# IMU.net
KiCad netlist of a schematic drawn in EAGLE
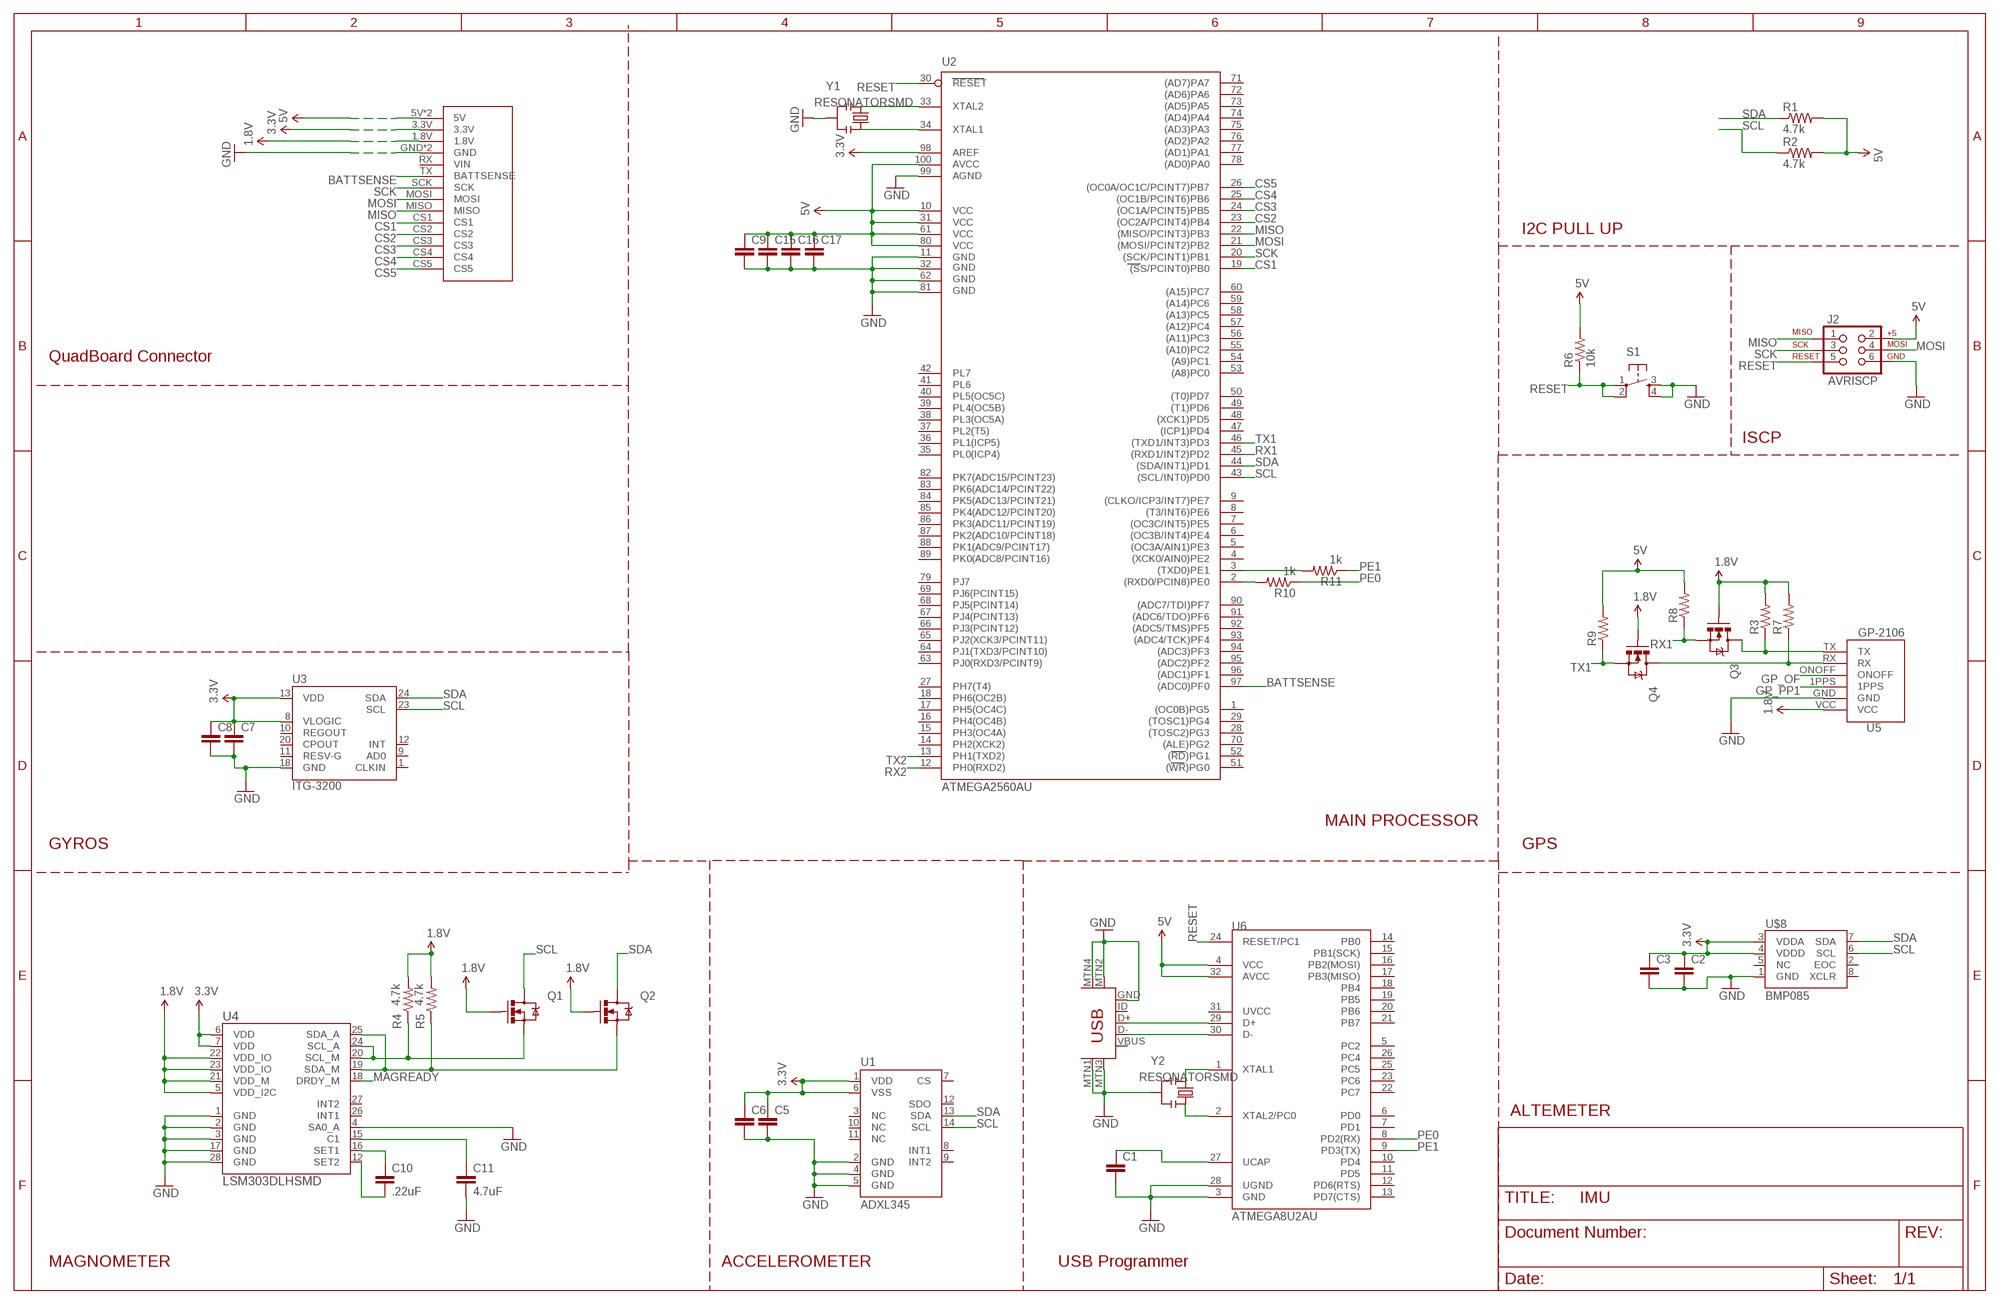
[diagram p0: schematic, sheet 1]

(export (version "E")
  (design (tool "Eeschema 10.0.6"))
  (components
    (comp (ref "C1")
      (value "CAP0805")
      (footprint "eagle-import:0805")
      (libsource (lib "eagle-import") (part "CAP0805"))
    )
    (comp (ref "C2")
      (value "CAP0805")
      (footprint "eagle-import:0805")
      (libsource (lib "eagle-import") (part "CAP0805"))
    )
    (comp (ref "C3")
      (value "CAP0805")
      (footprint "eagle-import:0805")
      (libsource (lib "eagle-import") (part "CAP0805"))
    )
    (comp (ref "C5")
      (value "CAP0805")
      (footprint "eagle-import:0805")
      (libsource (lib "eagle-import") (part "CAP0805"))
    )
    (comp (ref "C6")
      (value "CAP0805")
      (footprint "eagle-import:0805")
      (libsource (lib "eagle-import") (part "CAP0805"))
    )
    (comp (ref "C7")
      (value "CAP0805")
      (footprint "eagle-import:0805")
      (libsource (lib "eagle-import") (part "CAP0805"))
    )
    (comp (ref "C8")
      (value "CAP0805")
      (footprint "eagle-import:0805")
      (libsource (lib "eagle-import") (part "CAP0805"))
    )
    (comp (ref "C9")
      (value "CAP0805")
      (footprint "eagle-import:0805")
      (libsource (lib "eagle-import") (part "CAP0805"))
    )
    (comp (ref "C10")
      (value ".22uF")
      (footprint "eagle-import:0805")
      (libsource (lib "eagle-import") (part "CAP0805"))
    )
    (comp (ref "C11")
      (value "4.7uF")
      (footprint "eagle-import:0805")
      (libsource (lib "eagle-import") (part "CAP0805"))
    )
    (comp (ref "C15")
      (value "CAP0805")
      (footprint "eagle-import:0805")
      (libsource (lib "eagle-import") (part "CAP0805"))
    )
    (comp (ref "C16")
      (value "CAP0805")
      (footprint "eagle-import:0805")
      (libsource (lib "eagle-import") (part "CAP0805"))
    )
    (comp (ref "C17")
      (value "CAP0805")
      (footprint "eagle-import:0805")
      (libsource (lib "eagle-import") (part "CAP0805"))
    )
    (comp (ref "J2")
      (value "AVRISCP")
      (footprint "eagle-import:2X3")
      (libsource (lib "eagle-import") (part "AVR_SPI_PRG_6PTH"))
    )
    (comp (ref "Q1")
      (value "MOSFET-NCHANNELSMD")
      (footprint "eagle-import:SOT23-3")
      (libsource (lib "eagle-import") (part "MOSFET-NCHANNELSMD"))
    )
    (comp (ref "Q2")
      (value "MOSFET-NCHANNELSMD")
      (footprint "eagle-import:SOT23-3")
      (libsource (lib "eagle-import") (part "MOSFET-NCHANNELSMD"))
    )
    (comp (ref "Q3")
      (value "MOSFET-NCHANNELSMD")
      (footprint "eagle-import:SOT23-3")
      (libsource (lib "eagle-import") (part "MOSFET-NCHANNELSMD"))
    )
    (comp (ref "Q4")
      (value "MOSFET-NCHANNELSMD")
      (footprint "eagle-import:SOT23-3")
      (libsource (lib "eagle-import") (part "MOSFET-NCHANNELSMD"))
    )
    (comp (ref "R1")
      (value "4.7k")
      (footprint "eagle-import:0805")
      (libsource (lib "eagle-import") (part "RESISTOR0805-RES"))
    )
    (comp (ref "R2")
      (value "4.7k")
      (footprint "eagle-import:0805")
      (libsource (lib "eagle-import") (part "RESISTOR0805-RES"))
    )
    (comp (ref "R3")
      (value "RESISTOR0805-RES")
      (footprint "eagle-import:0805")
      (libsource (lib "eagle-import") (part "RESISTOR0805-RES"))
    )
    (comp (ref "R4")
      (value "4.7k")
      (footprint "eagle-import:0805")
      (libsource (lib "eagle-import") (part "RESISTOR0805-RES"))
    )
    (comp (ref "R5")
      (value "4.7k")
      (footprint "eagle-import:0805")
      (libsource (lib "eagle-import") (part "RESISTOR0805-RES"))
    )
    (comp (ref "R6")
      (value "10k")
      (footprint "eagle-import:0805")
      (libsource (lib "eagle-import") (part "RESISTOR0805-RES"))
    )
    (comp (ref "R7")
      (value "RESISTOR0805-RES")
      (footprint "eagle-import:0805")
      (libsource (lib "eagle-import") (part "RESISTOR0805-RES"))
    )
    (comp (ref "R8")
      (value "RESISTOR0805-RES")
      (footprint "eagle-import:0805")
      (libsource (lib "eagle-import") (part "RESISTOR0805-RES"))
    )
    (comp (ref "R9")
      (value "RESISTOR0805-RES")
      (footprint "eagle-import:0805")
      (libsource (lib "eagle-import") (part "RESISTOR0805-RES"))
    )
    (comp (ref "R10")
      (value "1k")
      (footprint "eagle-import:0805")
      (libsource (lib "eagle-import") (part "RESISTOR0805-RES"))
    )
    (comp (ref "R11")
      (value "1k")
      (footprint "eagle-import:0805")
      (libsource (lib "eagle-import") (part "RESISTOR0805-RES"))
    )
    (comp (ref "S1")
      (value "TAC_SWITCHSMD")
      (footprint "eagle-import:TACTILE_SWITCH_SMD")
      (libsource (lib "eagle-import") (part "TAC_SWITCHSMD"))
    )
    (comp (ref "U$1")
      (value "USB-MINIB-5PIN")
      (footprint "eagle-import:USB-MINIB")
      (libsource (lib "eagle-import") (part "USB-MINIB-5PIN"))
    )
    (comp (ref "U$4")
      (value "QUADBOARDEXT")
      (footprint "eagle-import:QUADBOARDEXT")
      (libsource (lib "eagle-import") (part "QUADBOARDEXT"))
    )
    (comp (ref "U$8")
      (value "BMP085")
      (footprint "eagle-import:BMP085")
      (libsource (lib "eagle-import") (part "BMP085"))
    )
    (comp (ref "U1")
      (value "ADXL345")
      (footprint "eagle-import:LGA14")
      (libsource (lib "eagle-import") (part "ADXL345"))
    )
    (comp (ref "U2")
      (value "ATMEGA2560AU")
      (footprint "eagle-import:TQFP100")
      (libsource (lib "eagle-import") (part "ATMEGA2560AU"))
    )
    (comp (ref "U3")
      (value "ITG-3200")
      (footprint "eagle-import:QFN-24")
      (libsource (lib "eagle-import") (part "ITG-3200"))
    )
    (comp (ref "U4")
      (value "LSM303DLHSMD")
      (footprint "eagle-import:LGA28-5X5")
      (libsource (lib "eagle-import") (part "LSM303DLHSMD"))
    )
    (comp (ref "U5")
      (value "GP-2106")
      (footprint "eagle-import:GP-2106")
      (libsource (lib "eagle-import") (part "GP-2106"))
    )
    (comp (ref "U6")
      (value "ATMEGA8U2AU")
      (footprint "eagle-import:TQFP32-08")
      (libsource (lib "eagle-import") (part "ATMEGA8U2AU"))
    )
    (comp (ref "Y1")
      (value "RESONATORSMD")
      (footprint "eagle-import:RESONATOR-SMD")
      (libsource (lib "eagle-import") (part "RESONATORSMD"))
    )
    (comp (ref "Y2")
      (value "RESONATORSMD")
      (footprint "eagle-import:RESONATOR-SMD")
      (libsource (lib "eagle-import") (part "RESONATORSMD"))
    )
  )
  (nets
    (net (code "1") (name "/BATTSENSE") (class "Default")
      (node (ref "U$4") (pin "TX") (pinfunction "BATTSENSE_TX") (pintype "bidirectional"))
      (node (ref "U2") (pin "97") (pinfunction "(ADC0)PF0_97") (pintype "bidirectional"))
    )
    (net (code "2") (name "/CS1") (class "Default")
      (node (ref "U$4") (pin "CS1") (pinfunction "CS1_CS1") (pintype "bidirectional"))
      (node (ref "U2") (pin "19") (pinfunction "(SS/PCINT0)PB0_19") (pintype "bidirectional"))
    )
    (net (code "3") (name "/CS2") (class "Default")
      (node (ref "U$4") (pin "CS2") (pinfunction "CS2_CS2") (pintype "bidirectional"))
      (node (ref "U2") (pin "23") (pinfunction "(OC2A/PCINT4)PB4_23") (pintype "bidirectional"))
    )
    (net (code "4") (name "/CS3") (class "Default")
      (node (ref "U$4") (pin "CS3") (pinfunction "CS3_CS3") (pintype "bidirectional"))
      (node (ref "U2") (pin "24") (pinfunction "(OC1A/PCINT5)PB5_24") (pintype "bidirectional"))
    )
    (net (code "5") (name "/CS4") (class "Default")
      (node (ref "U$4") (pin "CS4") (pinfunction "CS4_CS4") (pintype "bidirectional"))
      (node (ref "U2") (pin "25") (pinfunction "(OC1B/PCINT6)PB6_25") (pintype "bidirectional"))
    )
    (net (code "6") (name "/CS5") (class "Default")
      (node (ref "U$4") (pin "CS5") (pinfunction "CS5_CS5") (pintype "bidirectional"))
      (node (ref "U2") (pin "26") (pinfunction "(OC0A/OC1C/PCINT7)PB7_26") (pintype "bidirectional"))
    )
    (net (code "7") (name "/GP_OF") (class "Default")
      (node (ref "U5") (pin "ONOFF") (pinfunction "ONOFF_ONOFF") (pintype "bidirectional"))
    )
    (net (code "8") (name "/GP_PP1") (class "Default")
      (node (ref "U5") (pin "1PPS") (pinfunction "1PPS_1PPS") (pintype "bidirectional"))
    )
    (net (code "9") (name "/MAGREADY") (class "Default")
      (node (ref "U4") (pin "18") (pinfunction "DRDY_M_18") (pintype "bidirectional"))
    )
    (net (code "10") (name "/MISO") (class "Default")
      (node (ref "J2") (pin "1") (pinfunction "1_1") (pintype "passive"))
      (node (ref "U$4") (pin "MISO") (pinfunction "MISO_MISO") (pintype "bidirectional"))
      (node (ref "U2") (pin "22") (pinfunction "(MISO/PCINT3)PB3_22") (pintype "bidirectional"))
    )
    (net (code "11") (name "/MOSI") (class "Default")
      (node (ref "J2") (pin "4") (pinfunction "4_4") (pintype "passive"))
      (node (ref "U$4") (pin "MOSI") (pinfunction "MOSI_MOSI") (pintype "bidirectional"))
      (node (ref "U2") (pin "21") (pinfunction "(MOSI/PCINT2)PB2_21") (pintype "bidirectional"))
    )
    (net (code "12") (name "/PE0") (class "Default")
      (node (ref "R10") (pin "1") (pinfunction "1_1") (pintype "passive"))
      (node (ref "U6") (pin "8") (pinfunction "PD2(RX)_8") (pintype "bidirectional"))
    )
    (net (code "13") (name "/PE1") (class "Default")
      (node (ref "R11") (pin "1") (pinfunction "1_1") (pintype "passive"))
      (node (ref "U6") (pin "9") (pinfunction "PD3(TX)_9") (pintype "bidirectional"))
    )
    (net (code "14") (name "/RESET") (class "Default")
      (node (ref "J2") (pin "5") (pinfunction "5_5") (pintype "passive"))
      (node (ref "R6") (pin "1") (pinfunction "1_1") (pintype "passive"))
      (node (ref "S1") (pin "1") (pinfunction "1_1") (pintype "passive"))
      (node (ref "S1") (pin "2") (pinfunction "2_2") (pintype "passive"))
      (node (ref "U2") (pin "30") (pinfunction "RESET_30") (pintype "input"))
      (node (ref "U6") (pin "24") (pinfunction "RESET/PC1_24") (pintype "bidirectional"))
    )
    (net (code "15") (name "/RX1") (class "Default")
      (node (ref "Q3") (pin "2") (pinfunction "S_2") (pintype "passive"))
      (node (ref "R8") (pin "1") (pinfunction "1_1") (pintype "passive"))
      (node (ref "U2") (pin "45") (pinfunction "(RXD1/INT2)PD2_45") (pintype "bidirectional"))
    )
    (net (code "16") (name "/RX2") (class "Default")
      (node (ref "U2") (pin "12") (pinfunction "PH0(RXD2)_12") (pintype "bidirectional"))
    )
    (net (code "17") (name "/SCK") (class "Default")
      (node (ref "J2") (pin "3") (pinfunction "3_3") (pintype "passive"))
      (node (ref "U$4") (pin "SCK") (pinfunction "SCK_SCK") (pintype "bidirectional"))
      (node (ref "U2") (pin "20") (pinfunction "(SCK/PCINT1)PB1_20") (pintype "bidirectional"))
    )
    (net (code "18") (name "/SCL") (class "Default")
      (node (ref "Q1") (pin "3") (pinfunction "D_3") (pintype "passive"))
      (node (ref "R2") (pin "1") (pinfunction "1_1") (pintype "passive"))
      (node (ref "U$8") (pin "6") (pinfunction "SCL_6") (pintype "input"))
      (node (ref "U1") (pin "14") (pinfunction "SCL_14") (pintype "bidirectional"))
      (node (ref "U2") (pin "43") (pinfunction "(SCL/INT0)PD0_43") (pintype "bidirectional"))
      (node (ref "U3") (pin "23") (pinfunction "SCL_23") (pintype "bidirectional"))
    )
    (net (code "19") (name "/SDA") (class "Default")
      (node (ref "Q2") (pin "3") (pinfunction "D_3") (pintype "passive"))
      (node (ref "R1") (pin "1") (pinfunction "1_1") (pintype "passive"))
      (node (ref "U$8") (pin "7") (pinfunction "SDA_7") (pintype "bidirectional"))
      (node (ref "U1") (pin "13") (pinfunction "SDA_13") (pintype "bidirectional"))
      (node (ref "U2") (pin "44") (pinfunction "(SDA/INT1)PD1_44") (pintype "bidirectional"))
      (node (ref "U3") (pin "24") (pinfunction "SDA_24") (pintype "bidirectional"))
    )
    (net (code "20") (name "/TX1") (class "Default")
      (node (ref "Q4") (pin "2") (pinfunction "S_2") (pintype "passive"))
      (node (ref "R9") (pin "1") (pinfunction "1_1") (pintype "passive"))
      (node (ref "U2") (pin "46") (pinfunction "(TXD1/INT3)PD3_46") (pintype "bidirectional"))
    )
    (net (code "21") (name "/TX2") (class "Default")
      (node (ref "U2") (pin "13") (pinfunction "PH1(TXD2)_13") (pintype "bidirectional"))
    )
    (net (code "22") (name "1.8V") (class "Default")
      (node (ref "Q1") (pin "1") (pinfunction "G_1") (pintype "passive"))
      (node (ref "Q2") (pin "1") (pinfunction "G_1") (pintype "passive"))
      (node (ref "Q3") (pin "1") (pinfunction "G_1") (pintype "passive"))
      (node (ref "Q4") (pin "1") (pinfunction "G_1") (pintype "passive"))
      (node (ref "R3") (pin "2") (pinfunction "2_2") (pintype "passive"))
      (node (ref "R4") (pin "2") (pinfunction "2_2") (pintype "passive"))
      (node (ref "R5") (pin "2") (pinfunction "2_2") (pintype "passive"))
      (node (ref "R7") (pin "2") (pinfunction "2_2") (pintype "passive"))
      (node (ref "U$4") (pin "1.8V") (pinfunction "1.8V_1.8V") (pintype "bidirectional"))
      (node (ref "U4") (pin "21") (pinfunction "VDD_M_21") (pintype "bidirectional"))
      (node (ref "U4") (pin "22") (pinfunction "VDD_IO_22") (pintype "bidirectional"))
      (node (ref "U4") (pin "23") (pinfunction "VDD_IO_23") (pintype "bidirectional"))
      (node (ref "U4") (pin "5") (pinfunction "VDD_I2C_5") (pintype "bidirectional"))
      (node (ref "U5") (pin "VCC") (pinfunction "VCC_VCC") (pintype "bidirectional"))
    )
    (net (code "23") (name "3.3V") (class "Default")
      (node (ref "C2") (pin "1") (pinfunction "1_1") (pintype "passive"))
      (node (ref "C3") (pin "1") (pinfunction "1_1") (pintype "passive"))
      (node (ref "C5") (pin "1") (pinfunction "1_1") (pintype "passive"))
      (node (ref "C6") (pin "1") (pinfunction "1_1") (pintype "passive"))
      (node (ref "C7") (pin "1") (pinfunction "1_1") (pintype "passive"))
      (node (ref "C8") (pin "1") (pinfunction "1_1") (pintype "passive"))
      (node (ref "U$4") (pin "3.3V") (pinfunction "3.3V_3.3V") (pintype "bidirectional"))
      (node (ref "U$8") (pin "3") (pinfunction "VDDA_3") (pintype "power_in"))
      (node (ref "U$8") (pin "4") (pinfunction "VDDD_4") (pintype "power_in"))
      (node (ref "U1") (pin "1") (pinfunction "VDD_1") (pintype "bidirectional"))
      (node (ref "U1") (pin "6") (pinfunction "VSS_6") (pintype "bidirectional"))
      (node (ref "U2") (pin "98") (pinfunction "AREF_98") (pintype "bidirectional"))
      (node (ref "U3") (pin "13") (pinfunction "VDD_13") (pintype "bidirectional"))
      (node (ref "U3") (pin "8") (pinfunction "VLOGIC_8") (pintype "bidirectional"))
      (node (ref "U4") (pin "6") (pinfunction "VDD_6") (pintype "bidirectional"))
      (node (ref "U4") (pin "7") (pinfunction "VDD_7") (pintype "bidirectional"))
    )
    (net (code "24") (name "5V") (class "Default")
      (node (ref "C15") (pin "1") (pinfunction "1_1") (pintype "passive"))
      (node (ref "C16") (pin "1") (pinfunction "1_1") (pintype "passive"))
      (node (ref "C17") (pin "1") (pinfunction "1_1") (pintype "passive"))
      (node (ref "C9") (pin "1") (pinfunction "1_1") (pintype "passive"))
      (node (ref "J2") (pin "2") (pinfunction "2_2") (pintype "passive"))
      (node (ref "R1") (pin "2") (pinfunction "2_2") (pintype "passive"))
      (node (ref "R2") (pin "2") (pinfunction "2_2") (pintype "passive"))
      (node (ref "R6") (pin "2") (pinfunction "2_2") (pintype "passive"))
      (node (ref "R8") (pin "2") (pinfunction "2_2") (pintype "passive"))
      (node (ref "R9") (pin "2") (pinfunction "2_2") (pintype "passive"))
      (node (ref "U$4") (pin "5V") (pinfunction "5V_5V") (pintype "bidirectional"))
      (node (ref "U$4") (pin "5V1") (pinfunction "5V_5V1") (pintype "bidirectional"))
      (node (ref "U2") (pin "10") (pinfunction "VCC_10") (pintype "power_in"))
      (node (ref "U2") (pin "100") (pinfunction "AVCC_100") (pintype "power_in"))
      (node (ref "U2") (pin "31") (pinfunction "VCC1_31") (pintype "power_in"))
      (node (ref "U2") (pin "61") (pinfunction "VCC2_61") (pintype "power_in"))
      (node (ref "U2") (pin "80") (pinfunction "VCC3_80") (pintype "power_in"))
      (node (ref "U6") (pin "32") (pinfunction "AVCC_32") (pintype "bidirectional"))
      (node (ref "U6") (pin "4") (pinfunction "VCC_4") (pintype "bidirectional"))
    )
    (net (code "25") (name "GND") (class "Default")
      (node (ref "C1") (pin "2") (pinfunction "2_2") (pintype "passive"))
      (node (ref "C11") (pin "2") (pinfunction "2_2") (pintype "passive"))
      (node (ref "C15") (pin "2") (pinfunction "2_2") (pintype "passive"))
      (node (ref "C16") (pin "2") (pinfunction "2_2") (pintype "passive"))
      (node (ref "C17") (pin "2") (pinfunction "2_2") (pintype "passive"))
      (node (ref "C2") (pin "2") (pinfunction "2_2") (pintype "passive"))
      (node (ref "C3") (pin "2") (pinfunction "2_2") (pintype "passive"))
      (node (ref "C5") (pin "2") (pinfunction "2_2") (pintype "passive"))
      (node (ref "C6") (pin "2") (pinfunction "2_2") (pintype "passive"))
      (node (ref "C7") (pin "2") (pinfunction "2_2") (pintype "passive"))
      (node (ref "C8") (pin "2") (pinfunction "2_2") (pintype "passive"))
      (node (ref "C9") (pin "2") (pinfunction "2_2") (pintype "passive"))
      (node (ref "J2") (pin "6") (pinfunction "6_6") (pintype "passive"))
      (node (ref "S1") (pin "3") (pinfunction "3_3") (pintype "passive"))
      (node (ref "S1") (pin "4") (pinfunction "4_4") (pintype "passive"))
      (node (ref "U$1") (pin "GND") (pinfunction "GND_GND") (pintype "bidirectional"))
      (node (ref "U$1") (pin "MTN1") (pinfunction "MTN2_MTN1") (pintype "bidirectional"))
      (node (ref "U$1") (pin "MTN2") (pinfunction "MTN3_MTN2") (pintype "bidirectional"))
      (node (ref "U$1") (pin "MTN3") (pinfunction "MTN1_MTN3") (pintype "bidirectional"))
      (node (ref "U$1") (pin "MTN4") (pinfunction "MTN4_MTN4") (pintype "bidirectional"))
      (node (ref "U$4") (pin "GND") (pinfunction "GND_GND") (pintype "bidirectional"))
      (node (ref "U$4") (pin "GND1") (pinfunction "GND_GND1") (pintype "bidirectional"))
      (node (ref "U$8") (pin "1") (pinfunction "GND_1") (pintype "power_in"))
      (node (ref "U1") (pin "2") (pinfunction "GND_2") (pintype "bidirectional"))
      (node (ref "U1") (pin "4") (pinfunction "GND_4") (pintype "bidirectional"))
      (node (ref "U1") (pin "5") (pinfunction "GND_5") (pintype "bidirectional"))
      (node (ref "U2") (pin "11") (pinfunction "GND_11") (pintype "power_in"))
      (node (ref "U2") (pin "32") (pinfunction "GND1_32") (pintype "power_in"))
      (node (ref "U2") (pin "62") (pinfunction "GND2_62") (pintype "power_in"))
      (node (ref "U2") (pin "81") (pinfunction "GND3_81") (pintype "power_in"))
      (node (ref "U2") (pin "99") (pinfunction "AGND_99") (pintype "power_in"))
      (node (ref "U3") (pin "18") (pinfunction "GND_18") (pintype "bidirectional"))
      (node (ref "U4") (pin "1") (pinfunction "GND_1") (pintype "bidirectional"))
      (node (ref "U4") (pin "17") (pinfunction "GND_17") (pintype "bidirectional"))
      (node (ref "U4") (pin "2") (pinfunction "GND_2") (pintype "bidirectional"))
      (node (ref "U4") (pin "28") (pinfunction "GND_28") (pintype "bidirectional"))
      (node (ref "U4") (pin "3") (pinfunction "GND_3") (pintype "bidirectional"))
      (node (ref "U4") (pin "4") (pinfunction "SA0_A_4") (pintype "bidirectional"))
      (node (ref "U5") (pin "GND") (pinfunction "GND_GND") (pintype "bidirectional"))
      (node (ref "U6") (pin "28") (pinfunction "UGND_28") (pintype "bidirectional"))
      (node (ref "U6") (pin "3") (pinfunction "GND_3") (pintype "bidirectional"))
      (node (ref "Y1") (pin "2") (pinfunction "2_2") (pintype "passive"))
      (node (ref "Y2") (pin "2") (pinfunction "2_2") (pintype "passive"))
    )
    (net (code "26") (name "Net-(Q1-S)") (class "Default")
      (node (ref "Q1") (pin "2") (pinfunction "S_2") (pintype "passive"))
      (node (ref "R4") (pin "1") (pinfunction "1_1") (pintype "passive"))
      (node (ref "U4") (pin "20") (pinfunction "SCL_M_20") (pintype "bidirectional"))
      (node (ref "U4") (pin "24") (pinfunction "SCL_A_24") (pintype "bidirectional"))
    )
    (net (code "27") (name "Net-(Q2-S)") (class "Default")
      (node (ref "Q2") (pin "2") (pinfunction "S_2") (pintype "passive"))
      (node (ref "R5") (pin "1") (pinfunction "1_1") (pintype "passive"))
      (node (ref "U4") (pin "19") (pinfunction "SDA_M_19") (pintype "bidirectional"))
      (node (ref "U4") (pin "25") (pinfunction "SDA_A_25") (pintype "bidirectional"))
    )
    (net (code "28") (name "Net-(Q3-D)") (class "Default")
      (node (ref "Q3") (pin "3") (pinfunction "D_3") (pintype "passive"))
      (node (ref "R3") (pin "1") (pinfunction "1_1") (pintype "passive"))
      (node (ref "U5") (pin "TX") (pinfunction "TX_TX") (pintype "bidirectional"))
    )
    (net (code "29") (name "Net-(Q4-D)") (class "Default")
      (node (ref "Q4") (pin "3") (pinfunction "D_3") (pintype "passive"))
      (node (ref "R7") (pin "1") (pinfunction "1_1") (pintype "passive"))
      (node (ref "U5") (pin "RX") (pinfunction "RX_RX") (pintype "bidirectional"))
    )
    (net (code "30") (name "Net-(U2-(RXD0{slash}PCIN8)PE0)") (class "Default")
      (node (ref "R10") (pin "2") (pinfunction "2_2") (pintype "passive"))
      (node (ref "U2") (pin "2") (pinfunction "(RXD0/PCIN8)PE0_2") (pintype "bidirectional"))
    )
    (net (code "31") (name "Net-(U2-(TXD0)PE1)") (class "Default")
      (node (ref "R11") (pin "2") (pinfunction "2_2") (pintype "passive"))
      (node (ref "U2") (pin "3") (pinfunction "(TXD0)PE1_3") (pintype "bidirectional"))
    )
    (net (code "32") (name "Net-(U2-XTAL1)") (class "Default")
      (node (ref "U2") (pin "34") (pinfunction "XTAL1_34") (pintype "input"))
      (node (ref "Y1") (pin "3") (pinfunction "3_3") (pintype "passive"))
    )
    (net (code "33") (name "Net-(U2-XTAL2)") (class "Default")
      (node (ref "U2") (pin "33") (pinfunction "XTAL2_33") (pintype "output"))
      (node (ref "Y1") (pin "1") (pinfunction "1_1") (pintype "passive"))
    )
    (net (code "34") (name "Net-(U4-C1)") (class "Default")
      (node (ref "C11") (pin "1") (pinfunction "1_1") (pintype "passive"))
      (node (ref "U4") (pin "15") (pinfunction "C1_15") (pintype "bidirectional"))
    )
    (net (code "35") (name "Net-(U4-SET1)") (class "Default")
      (node (ref "C10") (pin "1") (pinfunction "1_1") (pintype "passive"))
      (node (ref "U4") (pin "16") (pinfunction "SET1_16") (pintype "bidirectional"))
    )
    (net (code "36") (name "Net-(U4-SET2)") (class "Default")
      (node (ref "C10") (pin "2") (pinfunction "2_2") (pintype "passive"))
      (node (ref "U4") (pin "12") (pinfunction "SET2_12") (pintype "bidirectional"))
    )
    (net (code "37") (name "Net-(U6-D+)") (class "Default")
      (node (ref "U$1") (pin "D+") (pinfunction "D+_D+") (pintype "bidirectional"))
      (node (ref "U6") (pin "29") (pinfunction "D+_29") (pintype "bidirectional"))
    )
    (net (code "38") (name "Net-(U6-D-)") (class "Default")
      (node (ref "U$1") (pin "D-") (pinfunction "D-_D-") (pintype "bidirectional"))
      (node (ref "U6") (pin "30") (pinfunction "D-_30") (pintype "bidirectional"))
    )
    (net (code "39") (name "Net-(U6-UCAP)") (class "Default")
      (node (ref "C1") (pin "1") (pinfunction "1_1") (pintype "passive"))
      (node (ref "U6") (pin "27") (pinfunction "UCAP_27") (pintype "bidirectional"))
    )
    (net (code "40") (name "Net-(U6-XTAL1)") (class "Default")
      (node (ref "U6") (pin "1") (pinfunction "XTAL1_1") (pintype "bidirectional"))
      (node (ref "Y2") (pin "1") (pinfunction "1_1") (pintype "passive"))
    )
    (net (code "41") (name "Net-(U6-XTAL2{slash}PC0)") (class "Default")
      (node (ref "U6") (pin "2") (pinfunction "XTAL2/PC0_2") (pintype "bidirectional"))
      (node (ref "Y2") (pin "3") (pinfunction "3_3") (pintype "passive"))
    )
    (net (code "42") (name "unconnected-(U$1-PadID)") (class "Default")
      (node (ref "U$1") (pin "ID") (pinfunction "ID_ID") (pintype "bidirectional"))
    )
    (net (code "43") (name "unconnected-(U$1-PadVBUS)") (class "Default")
      (node (ref "U$1") (pin "VBUS") (pinfunction "VBUS_VBUS") (pintype "bidirectional"))
    )
    (net (code "44") (name "unconnected-(U$4-VIN-PadRX)") (class "Default")
      (node (ref "U$4") (pin "RX") (pinfunction "VIN_RX") (pintype "bidirectional"))
    )
    (net (code "45") (name "unconnected-(U$8-EOC-Pad2)") (class "Default")
      (node (ref "U$8") (pin "2") (pinfunction "EOC_2") (pintype "output"))
    )
    (net (code "46") (name "unconnected-(U$8-NC-Pad5)") (class "Default")
      (node (ref "U$8") (pin "5") (pinfunction "NC_5") (pintype "bidirectional"))
    )
    (net (code "47") (name "unconnected-(U$8-XCLR-Pad8)") (class "Default")
      (node (ref "U$8") (pin "8") (pinfunction "XCLR_8") (pintype "input"))
    )
    (net (code "48") (name "unconnected-(U1-CS-Pad7)") (class "Default")
      (node (ref "U1") (pin "7") (pinfunction "CS_7") (pintype "bidirectional"))
    )
    (net (code "49") (name "unconnected-(U1-INT1-Pad8)") (class "Default")
      (node (ref "U1") (pin "8") (pinfunction "INT1_8") (pintype "bidirectional"))
    )
    (net (code "50") (name "unconnected-(U1-INT2-Pad9)") (class "Default")
      (node (ref "U1") (pin "9") (pinfunction "INT2_9") (pintype "bidirectional"))
    )
    (net (code "51") (name "unconnected-(U1-NC-Pad3)") (class "Default")
      (node (ref "U1") (pin "3") (pinfunction "NC_3") (pintype "bidirectional"))
    )
    (net (code "52") (name "unconnected-(U1-NC-Pad10)") (class "Default")
      (node (ref "U1") (pin "10") (pinfunction "NC_10") (pintype "bidirectional"))
    )
    (net (code "53") (name "unconnected-(U1-NC-Pad11)") (class "Default")
      (node (ref "U1") (pin "11") (pinfunction "NC_11") (pintype "bidirectional"))
    )
    (net (code "54") (name "unconnected-(U1-SDO-Pad12)") (class "Default")
      (node (ref "U1") (pin "12") (pinfunction "SDO_12") (pintype "bidirectional"))
    )
    (net (code "55") (name "unconnected-(U2-(A8)PC0-Pad53)") (class "Default")
      (node (ref "U2") (pin "53") (pinfunction "(A8)PC0_53") (pintype "bidirectional"))
    )
    (net (code "56") (name "unconnected-(U2-(A9)PC1-Pad54)") (class "Default")
      (node (ref "U2") (pin "54") (pinfunction "(A9)PC1_54") (pintype "bidirectional"))
    )
    (net (code "57") (name "unconnected-(U2-(A10)PC2-Pad55)") (class "Default")
      (node (ref "U2") (pin "55") (pinfunction "(A10)PC2_55") (pintype "bidirectional"))
    )
    (net (code "58") (name "unconnected-(U2-(A11)PC3-Pad56)") (class "Default")
      (node (ref "U2") (pin "56") (pinfunction "(A11)PC3_56") (pintype "bidirectional"))
    )
    (net (code "59") (name "unconnected-(U2-(A12)PC4-Pad57)") (class "Default")
      (node (ref "U2") (pin "57") (pinfunction "(A12)PC4_57") (pintype "bidirectional"))
    )
    (net (code "60") (name "unconnected-(U2-(A13)PC5-Pad58)") (class "Default")
      (node (ref "U2") (pin "58") (pinfunction "(A13)PC5_58") (pintype "bidirectional"))
    )
    (net (code "61") (name "unconnected-(U2-(A14)PC6-Pad59)") (class "Default")
      (node (ref "U2") (pin "59") (pinfunction "(A14)PC6_59") (pintype "bidirectional"))
    )
    (net (code "62") (name "unconnected-(U2-(A15)PC7-Pad60)") (class "Default")
      (node (ref "U2") (pin "60") (pinfunction "(A15)PC7_60") (pintype "bidirectional"))
    )
    (net (code "63") (name "unconnected-(U2-(AD0)PA0-Pad78)") (class "Default")
      (node (ref "U2") (pin "78") (pinfunction "(AD0)PA0_78") (pintype "bidirectional"))
    )
    (net (code "64") (name "unconnected-(U2-(AD1)PA1-Pad77)") (class "Default")
      (node (ref "U2") (pin "77") (pinfunction "(AD1)PA1_77") (pintype "bidirectional"))
    )
    (net (code "65") (name "unconnected-(U2-(AD2)PA2-Pad76)") (class "Default")
      (node (ref "U2") (pin "76") (pinfunction "(AD2)PA2_76") (pintype "bidirectional"))
    )
    (net (code "66") (name "unconnected-(U2-(AD3)PA3-Pad75)") (class "Default")
      (node (ref "U2") (pin "75") (pinfunction "(AD3)PA3_75") (pintype "bidirectional"))
    )
    (net (code "67") (name "unconnected-(U2-(AD4)PA4-Pad74)") (class "Default")
      (node (ref "U2") (pin "74") (pinfunction "(AD4)PA4_74") (pintype "bidirectional"))
    )
    (net (code "68") (name "unconnected-(U2-(AD5)PA5-Pad73)") (class "Default")
      (node (ref "U2") (pin "73") (pinfunction "(AD5)PA5_73") (pintype "bidirectional"))
    )
    (net (code "69") (name "unconnected-(U2-(AD6)PA6-Pad72)") (class "Default")
      (node (ref "U2") (pin "72") (pinfunction "(AD6)PA6_72") (pintype "bidirectional"))
    )
    (net (code "70") (name "unconnected-(U2-(AD7)PA7-Pad71)") (class "Default")
      (node (ref "U2") (pin "71") (pinfunction "(AD7)PA7_71") (pintype "bidirectional"))
    )
    (net (code "71") (name "unconnected-(U2-(ADC1)PF1-Pad96)") (class "Default")
      (node (ref "U2") (pin "96") (pinfunction "(ADC1)PF1_96") (pintype "bidirectional"))
    )
    (net (code "72") (name "unconnected-(U2-(ADC2)PF2-Pad95)") (class "Default")
      (node (ref "U2") (pin "95") (pinfunction "(ADC2)PF2_95") (pintype "bidirectional"))
    )
    (net (code "73") (name "unconnected-(U2-(ADC3)PF3-Pad94)") (class "Default")
      (node (ref "U2") (pin "94") (pinfunction "(ADC3)PF3_94") (pintype "bidirectional"))
    )
    (net (code "74") (name "unconnected-(U2-(ADC4{slash}TCK)PF4-Pad93)") (class "Default")
      (node (ref "U2") (pin "93") (pinfunction "(ADC4/TCK)PF4_93") (pintype "bidirectional"))
    )
    (net (code "75") (name "unconnected-(U2-(ADC5{slash}TMS)PF5-Pad92)") (class "Default")
      (node (ref "U2") (pin "92") (pinfunction "(ADC5/TMS)PF5_92") (pintype "bidirectional"))
    )
    (net (code "76") (name "unconnected-(U2-(ADC6{slash}TDO)PF6-Pad91)") (class "Default")
      (node (ref "U2") (pin "91") (pinfunction "(ADC6/TDO)PF6_91") (pintype "bidirectional"))
    )
    (net (code "77") (name "unconnected-(U2-(ADC7{slash}TDI)PF7-Pad90)") (class "Default")
      (node (ref "U2") (pin "90") (pinfunction "(ADC7/TDI)PF7_90") (pintype "bidirectional"))
    )
    (net (code "78") (name "unconnected-(U2-(ALE)PG2-Pad70)") (class "Default")
      (node (ref "U2") (pin "70") (pinfunction "(ALE)PG2_70") (pintype "bidirectional"))
    )
    (net (code "79") (name "unconnected-(U2-(CLKO{slash}ICP3{slash}INT7)PE7-Pad9)") (class "Default")
      (node (ref "U2") (pin "9") (pinfunction "(CLKO/ICP3/INT7)PE7_9") (pintype "bidirectional"))
    )
    (net (code "80") (name "unconnected-(U2-(ICP1)PD4-Pad47)") (class "Default")
      (node (ref "U2") (pin "47") (pinfunction "(ICP1)PD4_47") (pintype "bidirectional"))
    )
    (net (code "81") (name "unconnected-(U2-(OC0B)PG5-Pad1)") (class "Default")
      (node (ref "U2") (pin "1") (pinfunction "(OC0B)PG5_1") (pintype "bidirectional"))
    )
    (net (code "82") (name "unconnected-(U2-(OC3A{slash}AIN1)PE3-Pad5)") (class "Default")
      (node (ref "U2") (pin "5") (pinfunction "(OC3A/AIN1)PE3_5") (pintype "bidirectional"))
    )
    (net (code "83") (name "unconnected-(U2-(OC3B{slash}INT4)PE4-Pad6)") (class "Default")
      (node (ref "U2") (pin "6") (pinfunction "(OC3B/INT4)PE4_6") (pintype "bidirectional"))
    )
    (net (code "84") (name "unconnected-(U2-(OC3C{slash}INT5)PE5-Pad7)") (class "Default")
      (node (ref "U2") (pin "7") (pinfunction "(OC3C/INT5)PE5_7") (pintype "bidirectional"))
    )
    (net (code "85") (name "unconnected-(U2-(RD)PG1-Pad52)") (class "Default")
      (node (ref "U2") (pin "52") (pinfunction "(RD)PG1_52") (pintype "bidirectional"))
    )
    (net (code "86") (name "unconnected-(U2-(T0)PD7-Pad50)") (class "Default")
      (node (ref "U2") (pin "50") (pinfunction "(T0)PD7_50") (pintype "bidirectional"))
    )
    (net (code "87") (name "unconnected-(U2-(T1)PD6-Pad49)") (class "Default")
      (node (ref "U2") (pin "49") (pinfunction "(T1)PD6_49") (pintype "bidirectional"))
    )
    (net (code "88") (name "unconnected-(U2-(T3{slash}INT6)PE6-Pad8)") (class "Default")
      (node (ref "U2") (pin "8") (pinfunction "(T3/INT6)PE6_8") (pintype "bidirectional"))
    )
    (net (code "89") (name "unconnected-(U2-(TOSC1)PG4-Pad29)") (class "Default")
      (node (ref "U2") (pin "29") (pinfunction "(TOSC1)PG4_29") (pintype "bidirectional"))
    )
    (net (code "90") (name "unconnected-(U2-(TOSC2)PG3-Pad28)") (class "Default")
      (node (ref "U2") (pin "28") (pinfunction "(TOSC2)PG3_28") (pintype "bidirectional"))
    )
    (net (code "91") (name "unconnected-(U2-(WR)PG0-Pad51)") (class "Default")
      (node (ref "U2") (pin "51") (pinfunction "(WR)PG0_51") (pintype "bidirectional"))
    )
    (net (code "92") (name "unconnected-(U2-(XCK0{slash}AIN0)PE2-Pad4)") (class "Default")
      (node (ref "U2") (pin "4") (pinfunction "(XCK0/AIN0)PE2_4") (pintype "bidirectional"))
    )
    (net (code "93") (name "unconnected-(U2-(XCK1)PD5-Pad48)") (class "Default")
      (node (ref "U2") (pin "48") (pinfunction "(XCK1)PD5_48") (pintype "bidirectional"))
    )
    (net (code "94") (name "unconnected-(U2-PH2(XCK2)-Pad14)") (class "Default")
      (node (ref "U2") (pin "14") (pinfunction "PH2(XCK2)_14") (pintype "bidirectional"))
    )
    (net (code "95") (name "unconnected-(U2-PH3(OC4A)-Pad15)") (class "Default")
      (node (ref "U2") (pin "15") (pinfunction "PH3(OC4A)_15") (pintype "bidirectional"))
    )
    (net (code "96") (name "unconnected-(U2-PH4(OC4B)-Pad16)") (class "Default")
      (node (ref "U2") (pin "16") (pinfunction "PH4(OC4B)_16") (pintype "bidirectional"))
    )
    (net (code "97") (name "unconnected-(U2-PH5(OC4C)-Pad17)") (class "Default")
      (node (ref "U2") (pin "17") (pinfunction "PH5(OC4C)_17") (pintype "bidirectional"))
    )
    (net (code "98") (name "unconnected-(U2-PH6(OC2B)-Pad18)") (class "Default")
      (node (ref "U2") (pin "18") (pinfunction "PH6(OC2B)_18") (pintype "bidirectional"))
    )
    (net (code "99") (name "unconnected-(U2-PH7(T4)-Pad27)") (class "Default")
      (node (ref "U2") (pin "27") (pinfunction "PH7(T4)_27") (pintype "bidirectional"))
    )
    (net (code "100") (name "unconnected-(U2-PJ0(RXD3{slash}PCINT9)-Pad63)") (class "Default")
      (node (ref "U2") (pin "63") (pinfunction "PJ0(RXD3/PCINT9)_63") (pintype "bidirectional"))
    )
    (net (code "101") (name "unconnected-(U2-PJ1(TXD3{slash}PCINT10)-Pad64)") (class "Default")
      (node (ref "U2") (pin "64") (pinfunction "PJ1(TXD3/PCINT10)_64") (pintype "bidirectional"))
    )
    (net (code "102") (name "unconnected-(U2-PJ2(XCK3{slash}PCINT11)-Pad65)") (class "Default")
      (node (ref "U2") (pin "65") (pinfunction "PJ2(XCK3/PCINT11)_65") (pintype "bidirectional"))
    )
    (net (code "103") (name "unconnected-(U2-PJ3(PCINT12)-Pad66)") (class "Default")
      (node (ref "U2") (pin "66") (pinfunction "PJ3(PCINT12)_66") (pintype "bidirectional"))
    )
    (net (code "104") (name "unconnected-(U2-PJ4(PCINT13)-Pad67)") (class "Default")
      (node (ref "U2") (pin "67") (pinfunction "PJ4(PCINT13)_67") (pintype "bidirectional"))
    )
    (net (code "105") (name "unconnected-(U2-PJ5(PCINT14)-Pad68)") (class "Default")
      (node (ref "U2") (pin "68") (pinfunction "PJ5(PCINT14)_68") (pintype "bidirectional"))
    )
    (net (code "106") (name "unconnected-(U2-PJ6(PCINT15)-Pad69)") (class "Default")
      (node (ref "U2") (pin "69") (pinfunction "PJ6(PCINT15)_69") (pintype "bidirectional"))
    )
    (net (code "107") (name "unconnected-(U2-PJ7-Pad79)") (class "Default")
      (node (ref "U2") (pin "79") (pinfunction "PJ7_79") (pintype "bidirectional"))
    )
    (net (code "108") (name "unconnected-(U2-PK0(ADC8{slash}PCINT16)-Pad89)") (class "Default")
      (node (ref "U2") (pin "89") (pinfunction "PK0(ADC8/PCINT16)_89") (pintype "bidirectional"))
    )
    (net (code "109") (name "unconnected-(U2-PK1(ADC9{slash}PCINT17)-Pad88)") (class "Default")
      (node (ref "U2") (pin "88") (pinfunction "PK1(ADC9/PCINT17)_88") (pintype "bidirectional"))
    )
    (net (code "110") (name "unconnected-(U2-PK2(ADC10{slash}PCINT18)-Pad87)") (class "Default")
      (node (ref "U2") (pin "87") (pinfunction "PK2(ADC10/PCINT18)_87") (pintype "bidirectional"))
    )
    (net (code "111") (name "unconnected-(U2-PK3(ADC11{slash}PCINT19)-Pad86)") (class "Default")
      (node (ref "U2") (pin "86") (pinfunction "PK3(ADC11/PCINT19)_86") (pintype "bidirectional"))
    )
    (net (code "112") (name "unconnected-(U2-PK4(ADC12{slash}PCINT20)-Pad85)") (class "Default")
      (node (ref "U2") (pin "85") (pinfunction "PK4(ADC12/PCINT20)_85") (pintype "bidirectional"))
    )
    (net (code "113") (name "unconnected-(U2-PK5(ADC13{slash}PCINT21)-Pad84)") (class "Default")
      (node (ref "U2") (pin "84") (pinfunction "PK5(ADC13/PCINT21)_84") (pintype "bidirectional"))
    )
    (net (code "114") (name "unconnected-(U2-PK6(ADC14{slash}PCINT22)-Pad83)") (class "Default")
      (node (ref "U2") (pin "83") (pinfunction "PK6(ADC14/PCINT22)_83") (pintype "bidirectional"))
    )
    (net (code "115") (name "unconnected-(U2-PK7(ADC15{slash}PCINT23)-Pad82)") (class "Default")
      (node (ref "U2") (pin "82") (pinfunction "PK7(ADC15/PCINT23)_82") (pintype "bidirectional"))
    )
    (net (code "116") (name "unconnected-(U2-PL0(ICP4)-Pad35)") (class "Default")
      (node (ref "U2") (pin "35") (pinfunction "PL0(ICP4)_35") (pintype "bidirectional"))
    )
    (net (code "117") (name "unconnected-(U2-PL1(ICP5)-Pad36)") (class "Default")
      (node (ref "U2") (pin "36") (pinfunction "PL1(ICP5)_36") (pintype "bidirectional"))
    )
    (net (code "118") (name "unconnected-(U2-PL2(T5)-Pad37)") (class "Default")
      (node (ref "U2") (pin "37") (pinfunction "PL2(T5)_37") (pintype "bidirectional"))
    )
    (net (code "119") (name "unconnected-(U2-PL3(OC5A)-Pad38)") (class "Default")
      (node (ref "U2") (pin "38") (pinfunction "PL3(OC5A)_38") (pintype "bidirectional"))
    )
    (net (code "120") (name "unconnected-(U2-PL4(OC5B)-Pad39)") (class "Default")
      (node (ref "U2") (pin "39") (pinfunction "PL4(OC5B)_39") (pintype "bidirectional"))
    )
    (net (code "121") (name "unconnected-(U2-PL5(OC5C)-Pad40)") (class "Default")
      (node (ref "U2") (pin "40") (pinfunction "PL5(OC5C)_40") (pintype "bidirectional"))
    )
    (net (code "122") (name "unconnected-(U2-PL6-Pad41)") (class "Default")
      (node (ref "U2") (pin "41") (pinfunction "PL6_41") (pintype "bidirectional"))
    )
    (net (code "123") (name "unconnected-(U2-PL7-Pad42)") (class "Default")
      (node (ref "U2") (pin "42") (pinfunction "PL7_42") (pintype "bidirectional"))
    )
    (net (code "124") (name "unconnected-(U3-AD0-Pad9)") (class "Default")
      (node (ref "U3") (pin "9") (pinfunction "AD0_9") (pintype "bidirectional"))
    )
    (net (code "125") (name "unconnected-(U3-CLKIN-Pad1)") (class "Default")
      (node (ref "U3") (pin "1") (pinfunction "CLKIN_1") (pintype "bidirectional"))
    )
    (net (code "126") (name "unconnected-(U3-CPOUT-Pad20)") (class "Default")
      (node (ref "U3") (pin "20") (pinfunction "CPOUT_20") (pintype "bidirectional"))
    )
    (net (code "127") (name "unconnected-(U3-INT-Pad12)") (class "Default")
      (node (ref "U3") (pin "12") (pinfunction "INT_12") (pintype "bidirectional"))
    )
    (net (code "128") (name "unconnected-(U3-REGOUT-Pad10)") (class "Default")
      (node (ref "U3") (pin "10") (pinfunction "REGOUT_10") (pintype "bidirectional"))
    )
    (net (code "129") (name "unconnected-(U3-RESV-G-Pad11)") (class "Default")
      (node (ref "U3") (pin "11") (pinfunction "RESV-G_11") (pintype "bidirectional"))
    )
    (net (code "130") (name "unconnected-(U4-INT1-Pad26)") (class "Default")
      (node (ref "U4") (pin "26") (pinfunction "INT1_26") (pintype "bidirectional"))
    )
    (net (code "131") (name "unconnected-(U4-INT2-Pad27)") (class "Default")
      (node (ref "U4") (pin "27") (pinfunction "INT2_27") (pintype "bidirectional"))
    )
    (net (code "132") (name "unconnected-(U6-PB0-Pad14)") (class "Default")
      (node (ref "U6") (pin "14") (pinfunction "PB0_14") (pintype "bidirectional"))
    )
    (net (code "133") (name "unconnected-(U6-PB1(SCK)-Pad15)") (class "Default")
      (node (ref "U6") (pin "15") (pinfunction "PB1(SCK)_15") (pintype "bidirectional"))
    )
    (net (code "134") (name "unconnected-(U6-PB2(MOSI)-Pad16)") (class "Default")
      (node (ref "U6") (pin "16") (pinfunction "PB2(MOSI)_16") (pintype "bidirectional"))
    )
    (net (code "135") (name "unconnected-(U6-PB3(MISO)-Pad17)") (class "Default")
      (node (ref "U6") (pin "17") (pinfunction "PB3(MISO)_17") (pintype "bidirectional"))
    )
    (net (code "136") (name "unconnected-(U6-PB4-Pad18)") (class "Default")
      (node (ref "U6") (pin "18") (pinfunction "PB4_18") (pintype "bidirectional"))
    )
    (net (code "137") (name "unconnected-(U6-PB5-Pad19)") (class "Default")
      (node (ref "U6") (pin "19") (pinfunction "PB5_19") (pintype "bidirectional"))
    )
    (net (code "138") (name "unconnected-(U6-PB6-Pad20)") (class "Default")
      (node (ref "U6") (pin "20") (pinfunction "PB6_20") (pintype "bidirectional"))
    )
    (net (code "139") (name "unconnected-(U6-PB7-Pad21)") (class "Default")
      (node (ref "U6") (pin "21") (pinfunction "PB7_21") (pintype "bidirectional"))
    )
    (net (code "140") (name "unconnected-(U6-PC2-Pad5)") (class "Default")
      (node (ref "U6") (pin "5") (pinfunction "PC2_5") (pintype "bidirectional"))
    )
    (net (code "141") (name "unconnected-(U6-PC4-Pad26)") (class "Default")
      (node (ref "U6") (pin "26") (pinfunction "PC4_26") (pintype "bidirectional"))
    )
    (net (code "142") (name "unconnected-(U6-PC5-Pad25)") (class "Default")
      (node (ref "U6") (pin "25") (pinfunction "PC5_25") (pintype "bidirectional"))
    )
    (net (code "143") (name "unconnected-(U6-PC6-Pad23)") (class "Default")
      (node (ref "U6") (pin "23") (pinfunction "PC6_23") (pintype "bidirectional"))
    )
    (net (code "144") (name "unconnected-(U6-PC7-Pad22)") (class "Default")
      (node (ref "U6") (pin "22") (pinfunction "PC7_22") (pintype "bidirectional"))
    )
    (net (code "145") (name "unconnected-(U6-PD0-Pad6)") (class "Default")
      (node (ref "U6") (pin "6") (pinfunction "PD0_6") (pintype "bidirectional"))
    )
    (net (code "146") (name "unconnected-(U6-PD1-Pad7)") (class "Default")
      (node (ref "U6") (pin "7") (pinfunction "PD1_7") (pintype "bidirectional"))
    )
    (net (code "147") (name "unconnected-(U6-PD4-Pad10)") (class "Default")
      (node (ref "U6") (pin "10") (pinfunction "PD4_10") (pintype "bidirectional"))
    )
    (net (code "148") (name "unconnected-(U6-PD5-Pad11)") (class "Default")
      (node (ref "U6") (pin "11") (pinfunction "PD5_11") (pintype "bidirectional"))
    )
    (net (code "149") (name "unconnected-(U6-PD6(RTS)-Pad12)") (class "Default")
      (node (ref "U6") (pin "12") (pinfunction "PD6(RTS)_12") (pintype "bidirectional"))
    )
    (net (code "150") (name "unconnected-(U6-PD7(CTS)-Pad13)") (class "Default")
      (node (ref "U6") (pin "13") (pinfunction "PD7(CTS)_13") (pintype "bidirectional"))
    )
    (net (code "151") (name "unconnected-(U6-UVCC-Pad31)") (class "Default")
      (node (ref "U6") (pin "31") (pinfunction "UVCC_31") (pintype "bidirectional"))
    )
  )
)
